# MultiChannel_ADC.net
KiCad netlist of a schematic drawn in Altium Designer
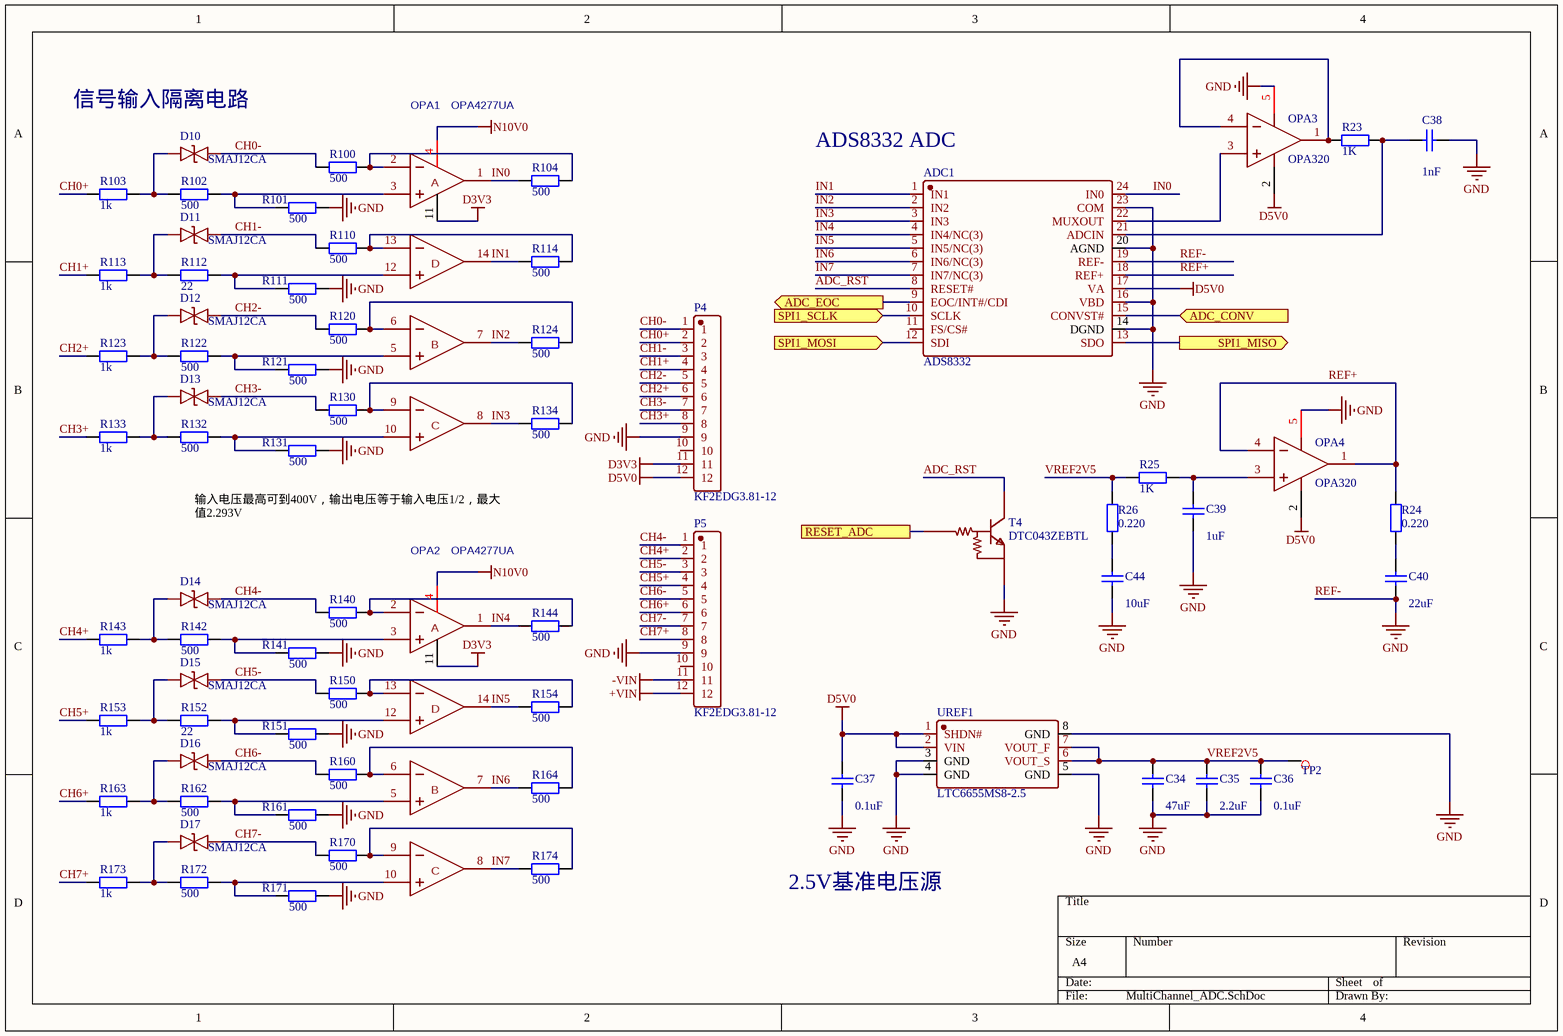
[diagram p0: MultiChannel_ADC.SchDoc]

(export (version "E")
  (design (tool "Eeschema 10.0.6"))
  (components
    (comp (ref "ADC1")
      (value "ADS8332")
      (footprint "TSSOP-24_L7.8-W4.4-P0.65-LS6.4-BL")
      (libsource (lib "NBIoT") (part "ADS8332"))
    )
    (comp (ref "C34")
      (value "47uF")
      (footprint "C1206")
      (description "Capacitor (Semiconductor SIM Model)")
      (fields (field (name "PUBLISHER") "Altium Limited"))
      (libsource (lib "Miscellaneous Devices") (part "Cap Semi"))
    )
    (comp (ref "C35")
      (value "2.2uF")
      (footprint "C1206")
      (description "Capacitor (Semiconductor SIM Model)")
      (fields (field (name "PUBLISHER") "Altium Limited"))
      (libsource (lib "Miscellaneous Devices") (part "Cap Semi"))
    )
    (comp (ref "C36")
      (value "0.1uF")
      (footprint "C1206")
      (description "Capacitor (Semiconductor SIM Model)")
      (fields (field (name "PUBLISHER") "Altium Limited"))
      (libsource (lib "Miscellaneous Devices") (part "Cap Semi"))
    )
    (comp (ref "C37")
      (value "0.1uF")
      (footprint "C1206")
      (description "Capacitor (Semiconductor SIM Model)")
      (fields (field (name "PUBLISHER") "Altium Limited"))
      (libsource (lib "Miscellaneous Devices") (part "Cap Semi"))
    )
    (comp (ref "C38")
      (value "1nF")
      (footprint "C1206")
      (description "Capacitor (Semiconductor SIM Model)")
      (fields (field (name "PUBLISHER") "Altium Limited"))
      (libsource (lib "Miscellaneous Devices") (part "Cap Semi"))
    )
    (comp (ref "C39")
      (value "1uF")
      (footprint "C1206")
      (description "Capacitor (Semiconductor SIM Model)")
      (fields (field (name "PUBLISHER") "Altium Limited"))
      (libsource (lib "Miscellaneous Devices") (part "Cap Semi"))
    )
    (comp (ref "C40")
      (value "22uF")
      (footprint "C1206")
      (description "Capacitor (Semiconductor SIM Model)")
      (fields (field (name "PUBLISHER") "Altium Limited"))
      (libsource (lib "Miscellaneous Devices") (part "Cap Semi"))
    )
    (comp (ref "C44")
      (value "10uF")
      (footprint "C1206")
      (description "Capacitor (Semiconductor SIM Model)")
      (fields (field (name "PUBLISHER") "Altium Limited"))
      (libsource (lib "Miscellaneous Devices") (part "Cap Semi"))
    )
    (comp (ref "D10")
      (value "SMAJ12CA")
      (footprint "SMB_L4.6-W3.6-LS5.3-BI")
      (libsource (lib "NBIoT") (part "SMBJ-XXCA"))
    )
    (comp (ref "D11")
      (value "SMAJ12CA")
      (footprint "SMB_L4.6-W3.6-LS5.3-BI")
      (libsource (lib "NBIoT") (part "SMBJ-XXCA"))
    )
    (comp (ref "D12")
      (value "SMAJ12CA")
      (footprint "SMB_L4.6-W3.6-LS5.3-BI")
      (libsource (lib "NBIoT") (part "SMBJ-XXCA"))
    )
    (comp (ref "D13")
      (value "SMAJ12CA")
      (footprint "SMB_L4.6-W3.6-LS5.3-BI")
      (libsource (lib "NBIoT") (part "SMBJ-XXCA"))
    )
    (comp (ref "D14")
      (value "SMAJ12CA")
      (footprint "SMB_L4.6-W3.6-LS5.3-BI")
      (libsource (lib "NBIoT") (part "SMBJ-XXCA"))
    )
    (comp (ref "D15")
      (value "SMAJ12CA")
      (footprint "SMB_L4.6-W3.6-LS5.3-BI")
      (libsource (lib "NBIoT") (part "SMBJ-XXCA"))
    )
    (comp (ref "D16")
      (value "SMAJ12CA")
      (footprint "SMB_L4.6-W3.6-LS5.3-BI")
      (libsource (lib "NBIoT") (part "SMBJ-XXCA"))
    )
    (comp (ref "D17")
      (value "SMAJ12CA")
      (footprint "SMB_L4.6-W3.6-LS5.3-BI")
      (libsource (lib "NBIoT") (part "SMBJ-XXCA"))
    )
    (comp (ref "OPA1")
      (value "OPA4277UA")
      (footprint "SOP-14_L8.6-W3.9-P1.27-LS6.0-BL")
      (fields (field (name "BOM_SUPPLIER PART") "C51504") (field (name "SUBPART_NO") "4"))
      (libsource (lib "OPA4227UA") (part "OPA4277UA"))
    )
    (comp (ref "OPA2")
      (value "OPA4277UA")
      (footprint "SOP-14_L8.6-W3.9-P1.27-LS6.0-BL")
      (fields (field (name "BOM_SUPPLIER PART") "C51504") (field (name "SUBPART_NO") "4"))
      (libsource (lib "OPA4227UA") (part "OPA4277UA"))
    )
    (comp (ref "OPA3")
      (value "OPA320")
      (footprint "SOT-23-5_L3.0-W1.7-P0.95-LS2.8-BR")
      (libsource (lib "NBIoT") (part "OPA320"))
    )
    (comp (ref "OPA4")
      (value "OPA320")
      (footprint "SOT-23-5_L3.0-W1.7-P0.95-LS2.8-BR")
      (libsource (lib "NBIoT") (part "OPA320"))
    )
    (comp (ref "P4")
      (value "KF2EDG3.81-12")
      (footprint "CONN-TH_12P-P3.81_KF2EDGV-3.81-12P")
      (libsource (lib "NBIoT") (part "KF2EDG3.81-12"))
    )
    (comp (ref "P5")
      (value "KF2EDG3.81-12")
      (footprint "CONN-TH_12P-P3.81_KF2EDGV-3.81-12P")
      (libsource (lib "NBIoT") (part "KF2EDG3.81-12"))
    )
    (comp (ref "R23")
      (value "1K")
      (footprint "0805_R")
      (description "0805贴片电阻")
      (libsource (lib "02-Miscellaneous_Devices_ZSF_Library") (part "Res_0805"))
    )
    (comp (ref "R24")
      (value "0.220")
      (footprint "0805_R")
      (description "0805贴片电阻")
      (libsource (lib "") (part "Res_0805_1"))
    )
    (comp (ref "R25")
      (value "1K")
      (footprint "0805_R")
      (description "0805贴片电阻")
      (libsource (lib "02-Miscellaneous_Devices_ZSF_Library") (part "Res_0805"))
    )
    (comp (ref "R26")
      (value "0.220")
      (footprint "0805_R")
      (description "0805贴片电阻")
      (libsource (lib "") (part "Res_0805_1"))
    )
    (comp (ref "R100")
      (value "500")
      (footprint "0805_R")
      (description "0805贴片电阻")
      (libsource (lib "02-Miscellaneous_Devices_ZSF_Library") (part "Res_0805"))
    )
    (comp (ref "R101")
      (value "500")
      (footprint "0805_R")
      (description "0805贴片电阻")
      (libsource (lib "02-Miscellaneous_Devices_ZSF_Library") (part "Res_0805"))
    )
    (comp (ref "R102")
      (value "500")
      (footprint "0805_R")
      (description "0805贴片电阻")
      (libsource (lib "02-Miscellaneous_Devices_ZSF_Library") (part "Res_0805"))
    )
    (comp (ref "R103")
      (value "1k")
      (footprint "0805_R")
      (description "0805贴片电阻")
      (libsource (lib "02-Miscellaneous_Devices_ZSF_Library") (part "Res_0805"))
    )
    (comp (ref "R104")
      (value "500")
      (footprint "0805_R")
      (description "0805贴片电阻")
      (libsource (lib "02-Miscellaneous_Devices_ZSF_Library") (part "Res_0805"))
    )
    (comp (ref "R110")
      (value "500")
      (footprint "0805_R")
      (description "0805贴片电阻")
      (libsource (lib "02-Miscellaneous_Devices_ZSF_Library") (part "Res_0805"))
    )
    (comp (ref "R111")
      (value "500")
      (footprint "0805_R")
      (description "0805贴片电阻")
      (libsource (lib "02-Miscellaneous_Devices_ZSF_Library") (part "Res_0805"))
    )
    (comp (ref "R112")
      (value "22")
      (footprint "0805_R")
      (description "0805贴片电阻")
      (libsource (lib "02-Miscellaneous_Devices_ZSF_Library") (part "Res_0805"))
    )
    (comp (ref "R113")
      (value "1k")
      (footprint "0805_R")
      (description "0805贴片电阻")
      (libsource (lib "02-Miscellaneous_Devices_ZSF_Library") (part "Res_0805"))
    )
    (comp (ref "R114")
      (value "500")
      (footprint "0805_R")
      (description "0805贴片电阻")
      (libsource (lib "02-Miscellaneous_Devices_ZSF_Library") (part "Res_0805"))
    )
    (comp (ref "R120")
      (value "500")
      (footprint "0805_R")
      (description "0805贴片电阻")
      (libsource (lib "02-Miscellaneous_Devices_ZSF_Library") (part "Res_0805"))
    )
    (comp (ref "R121")
      (value "500")
      (footprint "0805_R")
      (description "0805贴片电阻")
      (libsource (lib "02-Miscellaneous_Devices_ZSF_Library") (part "Res_0805"))
    )
    (comp (ref "R122")
      (value "500")
      (footprint "0805_R")
      (description "0805贴片电阻")
      (libsource (lib "02-Miscellaneous_Devices_ZSF_Library") (part "Res_0805"))
    )
    (comp (ref "R123")
      (value "1k")
      (footprint "0805_R")
      (description "0805贴片电阻")
      (libsource (lib "02-Miscellaneous_Devices_ZSF_Library") (part "Res_0805"))
    )
    (comp (ref "R124")
      (value "500")
      (footprint "0805_R")
      (description "0805贴片电阻")
      (libsource (lib "02-Miscellaneous_Devices_ZSF_Library") (part "Res_0805"))
    )
    (comp (ref "R130")
      (value "500")
      (footprint "0805_R")
      (description "0805贴片电阻")
      (libsource (lib "02-Miscellaneous_Devices_ZSF_Library") (part "Res_0805"))
    )
    (comp (ref "R131")
      (value "500")
      (footprint "0805_R")
      (description "0805贴片电阻")
      (libsource (lib "02-Miscellaneous_Devices_ZSF_Library") (part "Res_0805"))
    )
    (comp (ref "R132")
      (value "500")
      (footprint "0805_R")
      (description "0805贴片电阻")
      (libsource (lib "02-Miscellaneous_Devices_ZSF_Library") (part "Res_0805"))
    )
    (comp (ref "R133")
      (value "1k")
      (footprint "0805_R")
      (description "0805贴片电阻")
      (libsource (lib "02-Miscellaneous_Devices_ZSF_Library") (part "Res_0805"))
    )
    (comp (ref "R134")
      (value "500")
      (footprint "0805_R")
      (description "0805贴片电阻")
      (libsource (lib "02-Miscellaneous_Devices_ZSF_Library") (part "Res_0805"))
    )
    (comp (ref "R140")
      (value "500")
      (footprint "0805_R")
      (description "0805贴片电阻")
      (libsource (lib "02-Miscellaneous_Devices_ZSF_Library") (part "Res_0805"))
    )
    (comp (ref "R141")
      (value "500")
      (footprint "0805_R")
      (description "0805贴片电阻")
      (libsource (lib "02-Miscellaneous_Devices_ZSF_Library") (part "Res_0805"))
    )
    (comp (ref "R142")
      (value "500")
      (footprint "0805_R")
      (description "0805贴片电阻")
      (libsource (lib "02-Miscellaneous_Devices_ZSF_Library") (part "Res_0805"))
    )
    (comp (ref "R143")
      (value "1k")
      (footprint "0805_R")
      (description "0805贴片电阻")
      (libsource (lib "02-Miscellaneous_Devices_ZSF_Library") (part "Res_0805"))
    )
    (comp (ref "R144")
      (value "500")
      (footprint "0805_R")
      (description "0805贴片电阻")
      (libsource (lib "02-Miscellaneous_Devices_ZSF_Library") (part "Res_0805"))
    )
    (comp (ref "R150")
      (value "500")
      (footprint "0805_R")
      (description "0805贴片电阻")
      (libsource (lib "02-Miscellaneous_Devices_ZSF_Library") (part "Res_0805"))
    )
    (comp (ref "R151")
      (value "500")
      (footprint "0805_R")
      (description "0805贴片电阻")
      (libsource (lib "02-Miscellaneous_Devices_ZSF_Library") (part "Res_0805"))
    )
    (comp (ref "R152")
      (value "22")
      (footprint "0805_R")
      (description "0805贴片电阻")
      (libsource (lib "02-Miscellaneous_Devices_ZSF_Library") (part "Res_0805"))
    )
    (comp (ref "R153")
      (value "1k")
      (footprint "0805_R")
      (description "0805贴片电阻")
      (libsource (lib "02-Miscellaneous_Devices_ZSF_Library") (part "Res_0805"))
    )
    (comp (ref "R154")
      (value "500")
      (footprint "0805_R")
      (description "0805贴片电阻")
      (libsource (lib "02-Miscellaneous_Devices_ZSF_Library") (part "Res_0805"))
    )
    (comp (ref "R160")
      (value "500")
      (footprint "0805_R")
      (description "0805贴片电阻")
      (libsource (lib "02-Miscellaneous_Devices_ZSF_Library") (part "Res_0805"))
    )
    (comp (ref "R161")
      (value "500")
      (footprint "0805_R")
      (description "0805贴片电阻")
      (libsource (lib "02-Miscellaneous_Devices_ZSF_Library") (part "Res_0805"))
    )
    (comp (ref "R162")
      (value "500")
      (footprint "0805_R")
      (description "0805贴片电阻")
      (libsource (lib "02-Miscellaneous_Devices_ZSF_Library") (part "Res_0805"))
    )
    (comp (ref "R163")
      (value "1k")
      (footprint "0805_R")
      (description "0805贴片电阻")
      (libsource (lib "02-Miscellaneous_Devices_ZSF_Library") (part "Res_0805"))
    )
    (comp (ref "R164")
      (value "500")
      (footprint "0805_R")
      (description "0805贴片电阻")
      (libsource (lib "02-Miscellaneous_Devices_ZSF_Library") (part "Res_0805"))
    )
    (comp (ref "R170")
      (value "500")
      (footprint "0805_R")
      (description "0805贴片电阻")
      (libsource (lib "02-Miscellaneous_Devices_ZSF_Library") (part "Res_0805"))
    )
    (comp (ref "R171")
      (value "500")
      (footprint "0805_R")
      (description "0805贴片电阻")
      (libsource (lib "02-Miscellaneous_Devices_ZSF_Library") (part "Res_0805"))
    )
    (comp (ref "R172")
      (value "500")
      (footprint "0805_R")
      (description "0805贴片电阻")
      (libsource (lib "02-Miscellaneous_Devices_ZSF_Library") (part "Res_0805"))
    )
    (comp (ref "R173")
      (value "1k")
      (footprint "0805_R")
      (description "0805贴片电阻")
      (libsource (lib "02-Miscellaneous_Devices_ZSF_Library") (part "Res_0805"))
    )
    (comp (ref "R174")
      (value "500")
      (footprint "0805_R")
      (description "0805贴片电阻")
      (libsource (lib "02-Miscellaneous_Devices_ZSF_Library") (part "Res_0805"))
    )
    (comp (ref "T4")
      (value "DTC043ZEBTL")
      (footprint "SOT-416_L1.6-W0.8-P1.00-LS1.6-BR")
      (libsource (lib "NBIoT") (part "DTC043ZEBTL"))
    )
    (comp (ref "TP2")
      (value "Test-Point")
      (footprint "TP")
      (libsource (lib "03-EButterflyIntegratedLibrary") (part "Test-Point"))
    )
    (comp (ref "UREF1")
      (value "LTC6655MS8-2.5")
      (footprint "MSOP-8_L3.0-W3.0-P0.65-LS4.9-BL")
      (libsource (lib "NBIoT") (part "LTC6655MS8-5"))
    )
  )
  (nets
    (net (code "1") (name "+VIN") (class "Default")
      (node (ref "P5") (pin "12") (pinfunction "12_12") (pintype "passive"))
    )
    (net (code "2") (name "-VIN") (class "Default")
      (node (ref "P5") (pin "11") (pinfunction "11_11") (pintype "passive"))
    )
    (net (code "3") (name "/ADC_CONV") (class "Default")
      (node (ref "ADC1") (pin "15") (pinfunction "CONVST#_15") (pintype "passive"))
    )
    (net (code "4") (name "/ADC_EOC") (class "Default")
      (node (ref "ADC1") (pin "9") (pinfunction "EOC/INT#/CDI_9") (pintype "passive"))
    )
    (net (code "5") (name "/ADC_RST") (class "Default")
      (node (ref "ADC1") (pin "8") (pinfunction "RESET#_8") (pintype "passive"))
      (node (ref "T4") (pin "3") (pinfunction "C_3") (pintype "passive"))
    )
    (net (code "6") (name "/CH0+") (class "Default")
      (node (ref "P4") (pin "2") (pinfunction "2_2") (pintype "passive"))
      (node (ref "R103") (pin "2") (pinfunction "2_2") (pintype "passive"))
    )
    (net (code "7") (name "/CH0-") (class "Default")
      (node (ref "D10") (pin "1") (pinfunction "1_1") (pintype "passive"))
      (node (ref "P4") (pin "1") (pinfunction "1_1") (pintype "passive"))
      (node (ref "R100") (pin "2") (pinfunction "2_2") (pintype "passive"))
    )
    (net (code "8") (name "/CH1+") (class "Default")
      (node (ref "P4") (pin "4") (pinfunction "4_4") (pintype "passive"))
      (node (ref "R113") (pin "2") (pinfunction "2_2") (pintype "passive"))
    )
    (net (code "9") (name "/CH1-") (class "Default")
      (node (ref "D11") (pin "1") (pinfunction "1_1") (pintype "passive"))
      (node (ref "P4") (pin "3") (pinfunction "3_3") (pintype "passive"))
      (node (ref "R110") (pin "2") (pinfunction "2_2") (pintype "passive"))
    )
    (net (code "10") (name "/CH2+") (class "Default")
      (node (ref "P4") (pin "6") (pinfunction "6_6") (pintype "passive"))
      (node (ref "R123") (pin "2") (pinfunction "2_2") (pintype "passive"))
    )
    (net (code "11") (name "/CH2-") (class "Default")
      (node (ref "D12") (pin "1") (pinfunction "1_1") (pintype "passive"))
      (node (ref "P4") (pin "5") (pinfunction "5_5") (pintype "passive"))
      (node (ref "R120") (pin "2") (pinfunction "2_2") (pintype "passive"))
    )
    (net (code "12") (name "/CH3+") (class "Default")
      (node (ref "P4") (pin "8") (pinfunction "8_8") (pintype "passive"))
      (node (ref "R133") (pin "2") (pinfunction "2_2") (pintype "passive"))
    )
    (net (code "13") (name "/CH3-") (class "Default")
      (node (ref "D13") (pin "1") (pinfunction "1_1") (pintype "passive"))
      (node (ref "P4") (pin "7") (pinfunction "7_7") (pintype "passive"))
      (node (ref "R130") (pin "2") (pinfunction "2_2") (pintype "passive"))
    )
    (net (code "14") (name "/CH4+") (class "Default")
      (node (ref "P5") (pin "2") (pinfunction "2_2") (pintype "passive"))
      (node (ref "R143") (pin "2") (pinfunction "2_2") (pintype "passive"))
    )
    (net (code "15") (name "/CH4-") (class "Default")
      (node (ref "D14") (pin "1") (pinfunction "1_1") (pintype "passive"))
      (node (ref "P5") (pin "1") (pinfunction "1_1") (pintype "passive"))
      (node (ref "R140") (pin "2") (pinfunction "2_2") (pintype "passive"))
    )
    (net (code "16") (name "/CH5+") (class "Default")
      (node (ref "P5") (pin "4") (pinfunction "4_4") (pintype "passive"))
      (node (ref "R153") (pin "2") (pinfunction "2_2") (pintype "passive"))
    )
    (net (code "17") (name "/CH5-") (class "Default")
      (node (ref "D15") (pin "1") (pinfunction "1_1") (pintype "passive"))
      (node (ref "P5") (pin "3") (pinfunction "3_3") (pintype "passive"))
      (node (ref "R150") (pin "2") (pinfunction "2_2") (pintype "passive"))
    )
    (net (code "18") (name "/CH6+") (class "Default")
      (node (ref "P5") (pin "6") (pinfunction "6_6") (pintype "passive"))
      (node (ref "R163") (pin "2") (pinfunction "2_2") (pintype "passive"))
    )
    (net (code "19") (name "/CH6-") (class "Default")
      (node (ref "D16") (pin "1") (pinfunction "1_1") (pintype "passive"))
      (node (ref "P5") (pin "5") (pinfunction "5_5") (pintype "passive"))
      (node (ref "R160") (pin "2") (pinfunction "2_2") (pintype "passive"))
    )
    (net (code "20") (name "/CH7+") (class "Default")
      (node (ref "P5") (pin "8") (pinfunction "8_8") (pintype "passive"))
      (node (ref "R173") (pin "2") (pinfunction "2_2") (pintype "passive"))
    )
    (net (code "21") (name "/CH7-") (class "Default")
      (node (ref "D17") (pin "1") (pinfunction "1_1") (pintype "passive"))
      (node (ref "P5") (pin "7") (pinfunction "7_7") (pintype "passive"))
      (node (ref "R170") (pin "2") (pinfunction "2_2") (pintype "passive"))
    )
    (net (code "22") (name "/IN0") (class "Default")
      (node (ref "ADC1") (pin "24") (pinfunction "IN0_24") (pintype "passive"))
      (node (ref "OPA1") (pin "1") (pinfunction "OUT_A_1") (pintype "passive"))
      (node (ref "R104") (pin "2") (pinfunction "2_2") (pintype "passive"))
    )
    (net (code "23") (name "/IN1") (class "Default")
      (node (ref "ADC1") (pin "1") (pinfunction "IN1_1") (pintype "passive"))
      (node (ref "OPA1") (pin "14") (pinfunction "OUT_D_14") (pintype "passive"))
      (node (ref "R114") (pin "2") (pinfunction "2_2") (pintype "passive"))
    )
    (net (code "24") (name "/IN2") (class "Default")
      (node (ref "ADC1") (pin "2") (pinfunction "IN2_2") (pintype "passive"))
      (node (ref "OPA1") (pin "7") (pinfunction "OUT_B_7") (pintype "passive"))
      (node (ref "R124") (pin "2") (pinfunction "2_2") (pintype "passive"))
    )
    (net (code "25") (name "/IN3") (class "Default")
      (node (ref "ADC1") (pin "3") (pinfunction "IN3_3") (pintype "passive"))
      (node (ref "OPA1") (pin "8") (pinfunction "OUT_C_8") (pintype "passive"))
      (node (ref "R134") (pin "2") (pinfunction "2_2") (pintype "passive"))
    )
    (net (code "26") (name "/IN4") (class "Default")
      (node (ref "ADC1") (pin "4") (pinfunction "IN4/NC(3)_4") (pintype "passive"))
      (node (ref "OPA2") (pin "1") (pinfunction "OUT_A_1") (pintype "passive"))
      (node (ref "R144") (pin "2") (pinfunction "2_2") (pintype "passive"))
    )
    (net (code "27") (name "/IN5") (class "Default")
      (node (ref "ADC1") (pin "5") (pinfunction "IN5/NC(3)_5") (pintype "passive"))
      (node (ref "OPA2") (pin "14") (pinfunction "OUT_D_14") (pintype "passive"))
      (node (ref "R154") (pin "2") (pinfunction "2_2") (pintype "passive"))
    )
    (net (code "28") (name "/IN6") (class "Default")
      (node (ref "ADC1") (pin "6") (pinfunction "IN6/NC(3)_6") (pintype "passive"))
      (node (ref "OPA2") (pin "7") (pinfunction "OUT_B_7") (pintype "passive"))
      (node (ref "R164") (pin "2") (pinfunction "2_2") (pintype "passive"))
    )
    (net (code "29") (name "/IN7") (class "Default")
      (node (ref "ADC1") (pin "7") (pinfunction "IN7/NC(3)_7") (pintype "passive"))
      (node (ref "OPA2") (pin "8") (pinfunction "OUT_C_8") (pintype "passive"))
      (node (ref "R174") (pin "2") (pinfunction "2_2") (pintype "passive"))
    )
    (net (code "30") (name "/REF+") (class "Default")
      (node (ref "ADC1") (pin "18") (pinfunction "REF+_18") (pintype "passive"))
      (node (ref "OPA4") (pin "1") (pinfunction "OUT_1") (pintype "passive"))
      (node (ref "OPA4") (pin "4") (pinfunction "IN-_4") (pintype "passive"))
      (node (ref "R24") (pin "1") (pinfunction "1_1") (pintype "passive"))
    )
    (net (code "31") (name "/RESET_ADC") (class "Default")
      (node (ref "T4") (pin "1") (pinfunction "B_1") (pintype "passive"))
    )
    (net (code "32") (name "/SPI1_MISO") (class "Default")
      (node (ref "ADC1") (pin "13") (pinfunction "SDO_13") (pintype "passive"))
    )
    (net (code "33") (name "/SPI1_MOSI") (class "Default")
      (node (ref "ADC1") (pin "12") (pinfunction "SDI_12") (pintype "passive"))
    )
    (net (code "34") (name "/SPI1_SCLK") (class "Default")
      (node (ref "ADC1") (pin "10") (pinfunction "SCLK_10") (pintype "passive"))
    )
    (net (code "35") (name "/VREF2V5") (class "Default")
      (node (ref "C34") (pin "1") (pinfunction "1_1") (pintype "passive"))
      (node (ref "C35") (pin "1") (pinfunction "1_1") (pintype "passive"))
      (node (ref "C36") (pin "1") (pinfunction "1_1") (pintype "passive"))
      (node (ref "R25") (pin "2") (pinfunction "2_2") (pintype "passive"))
      (node (ref "R26") (pin "1") (pinfunction "1_1") (pintype "passive"))
      (node (ref "TP2") (pin "1") (pinfunction "0_1") (pintype "passive"))
      (node (ref "UREF1") (pin "6") (pinfunction "VOUT_S_6") (pintype "passive"))
      (node (ref "UREF1") (pin "7") (pinfunction "VOUT_F_7") (pintype "passive"))
    )
    (net (code "36") (name "D3V3") (class "Default")
      (node (ref "OPA1") (pin "11") (pinfunction "V-_11") (pintype "passive"))
      (node (ref "OPA2") (pin "11") (pinfunction "V-_11") (pintype "passive"))
      (node (ref "P4") (pin "11") (pinfunction "11_11") (pintype "passive"))
    )
    (net (code "37") (name "D5V0") (class "Default")
      (node (ref "ADC1") (pin "17") (pinfunction "VA_17") (pintype "passive"))
      (node (ref "C37") (pin "1") (pinfunction "1_1") (pintype "passive"))
      (node (ref "OPA3") (pin "2") (pinfunction "V-_2") (pintype "passive"))
      (node (ref "OPA4") (pin "2") (pinfunction "V-_2") (pintype "passive"))
      (node (ref "P4") (pin "12") (pinfunction "12_12") (pintype "passive"))
      (node (ref "UREF1") (pin "1") (pinfunction "SHDN#_1") (pintype "passive"))
      (node (ref "UREF1") (pin "2") (pinfunction "VIN_2") (pintype "passive"))
    )
    (net (code "38") (name "GND") (class "Default")
      (node (ref "ADC1") (pin "14") (pinfunction "DGND_14") (pintype "passive"))
      (node (ref "ADC1") (pin "16") (pinfunction "VBD_16") (pintype "passive"))
      (node (ref "ADC1") (pin "19") (pinfunction "REF-_19") (pintype "passive"))
      (node (ref "ADC1") (pin "20") (pinfunction "AGND_20") (pintype "passive"))
      (node (ref "ADC1") (pin "23") (pinfunction "COM_23") (pintype "passive"))
      (node (ref "C34") (pin "2") (pinfunction "2_2") (pintype "passive"))
      (node (ref "C35") (pin "2") (pinfunction "2_2") (pintype "passive"))
      (node (ref "C36") (pin "2") (pinfunction "2_2") (pintype "passive"))
      (node (ref "C37") (pin "2") (pinfunction "2_2") (pintype "passive"))
      (node (ref "C38") (pin "2") (pinfunction "2_2") (pintype "passive"))
      (node (ref "C39") (pin "1") (pinfunction "1_1") (pintype "passive"))
      (node (ref "C40") (pin "1") (pinfunction "1_1") (pintype "passive"))
      (node (ref "C44") (pin "1") (pinfunction "1_1") (pintype "passive"))
      (node (ref "OPA3") (pin "5") (pinfunction "V+_5") (pintype "passive"))
      (node (ref "OPA4") (pin "5") (pinfunction "V+_5") (pintype "passive"))
      (node (ref "P4") (pin "9") (pinfunction "9_9") (pintype "passive"))
      (node (ref "P5") (pin "9") (pinfunction "9_9") (pintype "passive"))
      (node (ref "R101") (pin "1") (pinfunction "1_1") (pintype "passive"))
      (node (ref "R111") (pin "1") (pinfunction "1_1") (pintype "passive"))
      (node (ref "R121") (pin "1") (pinfunction "1_1") (pintype "passive"))
      (node (ref "R131") (pin "1") (pinfunction "1_1") (pintype "passive"))
      (node (ref "R141") (pin "1") (pinfunction "1_1") (pintype "passive"))
      (node (ref "R151") (pin "1") (pinfunction "1_1") (pintype "passive"))
      (node (ref "R161") (pin "1") (pinfunction "1_1") (pintype "passive"))
      (node (ref "R171") (pin "1") (pinfunction "1_1") (pintype "passive"))
      (node (ref "T4") (pin "2") (pinfunction "E_2") (pintype "passive"))
      (node (ref "UREF1") (pin "3") (pinfunction "GND_3") (pintype "passive"))
      (node (ref "UREF1") (pin "4") (pinfunction "GND_4") (pintype "passive"))
      (node (ref "UREF1") (pin "5") (pinfunction "GND_5") (pintype "passive"))
      (node (ref "UREF1") (pin "8") (pinfunction "GND_8") (pintype "passive"))
    )
    (net (code "39") (name "N10V0") (class "Default")
      (node (ref "OPA1") (pin "4") (pinfunction "V+_4") (pintype "passive"))
      (node (ref "OPA2") (pin "4") (pinfunction "V+_4") (pintype "passive"))
    )
    (net (code "40") (name "Net-(ADC1-ADCIN)") (class "Default")
      (node (ref "ADC1") (pin "21") (pinfunction "ADCIN_21") (pintype "passive"))
      (node (ref "C38") (pin "1") (pinfunction "1_1") (pintype "passive"))
      (node (ref "R23") (pin "1") (pinfunction "1_1") (pintype "passive"))
    )
    (net (code "41") (name "Net-(ADC1-MUXOUT)") (class "Default")
      (node (ref "ADC1") (pin "22") (pinfunction "MUXOUT_22") (pintype "passive"))
      (node (ref "OPA3") (pin "3") (pinfunction "IN+_3") (pintype "passive"))
    )
    (net (code "42") (name "Net-(C40-Pad2)") (class "Default")
      (node (ref "C40") (pin "2") (pinfunction "2_2") (pintype "passive"))
      (node (ref "R24") (pin "2") (pinfunction "2_2") (pintype "passive"))
    )
    (net (code "43") (name "Net-(C44-Pad2)") (class "Default")
      (node (ref "C44") (pin "2") (pinfunction "2_2") (pintype "passive"))
      (node (ref "R26") (pin "2") (pinfunction "2_2") (pintype "passive"))
    )
    (net (code "44") (name "Net-(D10-Pad2)") (class "Default")
      (node (ref "D10") (pin "2") (pinfunction "2_2") (pintype "passive"))
      (node (ref "R102") (pin "2") (pinfunction "2_2") (pintype "passive"))
      (node (ref "R103") (pin "1") (pinfunction "1_1") (pintype "passive"))
    )
    (net (code "45") (name "Net-(D11-Pad2)") (class "Default")
      (node (ref "D11") (pin "2") (pinfunction "2_2") (pintype "passive"))
      (node (ref "R112") (pin "2") (pinfunction "2_2") (pintype "passive"))
      (node (ref "R113") (pin "1") (pinfunction "1_1") (pintype "passive"))
    )
    (net (code "46") (name "Net-(D12-Pad2)") (class "Default")
      (node (ref "D12") (pin "2") (pinfunction "2_2") (pintype "passive"))
      (node (ref "R122") (pin "2") (pinfunction "2_2") (pintype "passive"))
      (node (ref "R123") (pin "1") (pinfunction "1_1") (pintype "passive"))
    )
    (net (code "47") (name "Net-(D13-Pad2)") (class "Default")
      (node (ref "D13") (pin "2") (pinfunction "2_2") (pintype "passive"))
      (node (ref "R132") (pin "2") (pinfunction "2_2") (pintype "passive"))
      (node (ref "R133") (pin "1") (pinfunction "1_1") (pintype "passive"))
    )
    (net (code "48") (name "Net-(D14-Pad2)") (class "Default")
      (node (ref "D14") (pin "2") (pinfunction "2_2") (pintype "passive"))
      (node (ref "R142") (pin "2") (pinfunction "2_2") (pintype "passive"))
      (node (ref "R143") (pin "1") (pinfunction "1_1") (pintype "passive"))
    )
    (net (code "49") (name "Net-(D15-Pad2)") (class "Default")
      (node (ref "D15") (pin "2") (pinfunction "2_2") (pintype "passive"))
      (node (ref "R152") (pin "2") (pinfunction "2_2") (pintype "passive"))
      (node (ref "R153") (pin "1") (pinfunction "1_1") (pintype "passive"))
    )
    (net (code "50") (name "Net-(D16-Pad2)") (class "Default")
      (node (ref "D16") (pin "2") (pinfunction "2_2") (pintype "passive"))
      (node (ref "R162") (pin "2") (pinfunction "2_2") (pintype "passive"))
      (node (ref "R163") (pin "1") (pinfunction "1_1") (pintype "passive"))
    )
    (net (code "51") (name "Net-(D17-Pad2)") (class "Default")
      (node (ref "D17") (pin "2") (pinfunction "2_2") (pintype "passive"))
      (node (ref "R172") (pin "2") (pinfunction "2_2") (pintype "passive"))
      (node (ref "R173") (pin "1") (pinfunction "1_1") (pintype "passive"))
    )
    (net (code "52") (name "Net-(OPA1-+IN_A)") (class "Default")
      (node (ref "OPA1") (pin "3") (pinfunction "+IN_A_3") (pintype "passive"))
      (node (ref "R101") (pin "2") (pinfunction "2_2") (pintype "passive"))
      (node (ref "R102") (pin "1") (pinfunction "1_1") (pintype "passive"))
    )
    (net (code "53") (name "Net-(OPA1-+IN_B)") (class "Default")
      (node (ref "OPA1") (pin "5") (pinfunction "+IN_B_5") (pintype "passive"))
      (node (ref "R121") (pin "2") (pinfunction "2_2") (pintype "passive"))
      (node (ref "R122") (pin "1") (pinfunction "1_1") (pintype "passive"))
    )
    (net (code "54") (name "Net-(OPA1-+IN_C)") (class "Default")
      (node (ref "OPA1") (pin "10") (pinfunction "+IN_C_10") (pintype "passive"))
      (node (ref "R131") (pin "2") (pinfunction "2_2") (pintype "passive"))
      (node (ref "R132") (pin "1") (pinfunction "1_1") (pintype "passive"))
    )
    (net (code "55") (name "Net-(OPA1-+IN_D)") (class "Default")
      (node (ref "OPA1") (pin "12") (pinfunction "+IN_D_12") (pintype "passive"))
      (node (ref "R111") (pin "2") (pinfunction "2_2") (pintype "passive"))
      (node (ref "R112") (pin "1") (pinfunction "1_1") (pintype "passive"))
    )
    (net (code "56") (name "Net-(OPA1--IN_A)") (class "Default")
      (node (ref "OPA1") (pin "2") (pinfunction "-IN_A_2") (pintype "passive"))
      (node (ref "R100") (pin "1") (pinfunction "1_1") (pintype "passive"))
      (node (ref "R104") (pin "1") (pinfunction "1_1") (pintype "passive"))
    )
    (net (code "57") (name "Net-(OPA1--IN_B)") (class "Default")
      (node (ref "OPA1") (pin "6") (pinfunction "-IN_B_6") (pintype "passive"))
      (node (ref "R120") (pin "1") (pinfunction "1_1") (pintype "passive"))
      (node (ref "R124") (pin "1") (pinfunction "1_1") (pintype "passive"))
    )
    (net (code "58") (name "Net-(OPA1--IN_C)") (class "Default")
      (node (ref "OPA1") (pin "9") (pinfunction "-IN_C_9") (pintype "passive"))
      (node (ref "R130") (pin "1") (pinfunction "1_1") (pintype "passive"))
      (node (ref "R134") (pin "1") (pinfunction "1_1") (pintype "passive"))
    )
    (net (code "59") (name "Net-(OPA1--IN_D)") (class "Default")
      (node (ref "OPA1") (pin "13") (pinfunction "-IN_D_13") (pintype "passive"))
      (node (ref "R110") (pin "1") (pinfunction "1_1") (pintype "passive"))
      (node (ref "R114") (pin "1") (pinfunction "1_1") (pintype "passive"))
    )
    (net (code "60") (name "Net-(OPA2-+IN_A)") (class "Default")
      (node (ref "OPA2") (pin "3") (pinfunction "+IN_A_3") (pintype "passive"))
      (node (ref "R141") (pin "2") (pinfunction "2_2") (pintype "passive"))
      (node (ref "R142") (pin "1") (pinfunction "1_1") (pintype "passive"))
    )
    (net (code "61") (name "Net-(OPA2-+IN_B)") (class "Default")
      (node (ref "OPA2") (pin "5") (pinfunction "+IN_B_5") (pintype "passive"))
      (node (ref "R161") (pin "2") (pinfunction "2_2") (pintype "passive"))
      (node (ref "R162") (pin "1") (pinfunction "1_1") (pintype "passive"))
    )
    (net (code "62") (name "Net-(OPA2-+IN_C)") (class "Default")
      (node (ref "OPA2") (pin "10") (pinfunction "+IN_C_10") (pintype "passive"))
      (node (ref "R171") (pin "2") (pinfunction "2_2") (pintype "passive"))
      (node (ref "R172") (pin "1") (pinfunction "1_1") (pintype "passive"))
    )
    (net (code "63") (name "Net-(OPA2-+IN_D)") (class "Default")
      (node (ref "OPA2") (pin "12") (pinfunction "+IN_D_12") (pintype "passive"))
      (node (ref "R151") (pin "2") (pinfunction "2_2") (pintype "passive"))
      (node (ref "R152") (pin "1") (pinfunction "1_1") (pintype "passive"))
    )
    (net (code "64") (name "Net-(OPA2--IN_A)") (class "Default")
      (node (ref "OPA2") (pin "2") (pinfunction "-IN_A_2") (pintype "passive"))
      (node (ref "R140") (pin "1") (pinfunction "1_1") (pintype "passive"))
      (node (ref "R144") (pin "1") (pinfunction "1_1") (pintype "passive"))
    )
    (net (code "65") (name "Net-(OPA2--IN_B)") (class "Default")
      (node (ref "OPA2") (pin "6") (pinfunction "-IN_B_6") (pintype "passive"))
      (node (ref "R160") (pin "1") (pinfunction "1_1") (pintype "passive"))
      (node (ref "R164") (pin "1") (pinfunction "1_1") (pintype "passive"))
    )
    (net (code "66") (name "Net-(OPA2--IN_C)") (class "Default")
      (node (ref "OPA2") (pin "9") (pinfunction "-IN_C_9") (pintype "passive"))
      (node (ref "R170") (pin "1") (pinfunction "1_1") (pintype "passive"))
      (node (ref "R174") (pin "1") (pinfunction "1_1") (pintype "passive"))
    )
    (net (code "67") (name "Net-(OPA2--IN_D)") (class "Default")
      (node (ref "OPA2") (pin "13") (pinfunction "-IN_D_13") (pintype "passive"))
      (node (ref "R150") (pin "1") (pinfunction "1_1") (pintype "passive"))
      (node (ref "R154") (pin "1") (pinfunction "1_1") (pintype "passive"))
    )
    (net (code "68") (name "Net-(OPA3-IN-)") (class "Default")
      (node (ref "OPA3") (pin "1") (pinfunction "OUT_1") (pintype "passive"))
      (node (ref "OPA3") (pin "4") (pinfunction "IN-_4") (pintype "passive"))
      (node (ref "R23") (pin "2") (pinfunction "2_2") (pintype "passive"))
    )
    (net (code "69") (name "Net-(OPA4-IN+)") (class "Default")
      (node (ref "C39") (pin "2") (pinfunction "2_2") (pintype "passive"))
      (node (ref "OPA4") (pin "3") (pinfunction "IN+_3") (pintype "passive"))
      (node (ref "R25") (pin "1") (pinfunction "1_1") (pintype "passive"))
    )
    (net (code "70") (name "unconnected-(ADC1-FS{slash}CS#-Pad11)") (class "Default")
      (node (ref "ADC1") (pin "11") (pinfunction "FS/CS#_11") (pintype "passive"))
    )
    (net (code "71") (name "unconnected-(P4-Pad10)") (class "Default")
      (node (ref "P4") (pin "10") (pinfunction "10_10") (pintype "passive"))
    )
    (net (code "72") (name "unconnected-(P5-Pad10)") (class "Default")
      (node (ref "P5") (pin "10") (pinfunction "10_10") (pintype "passive"))
    )
  )
)
